# pilotage_moteur.net
KiCad netlist of a schematic drawn in Altium Designer
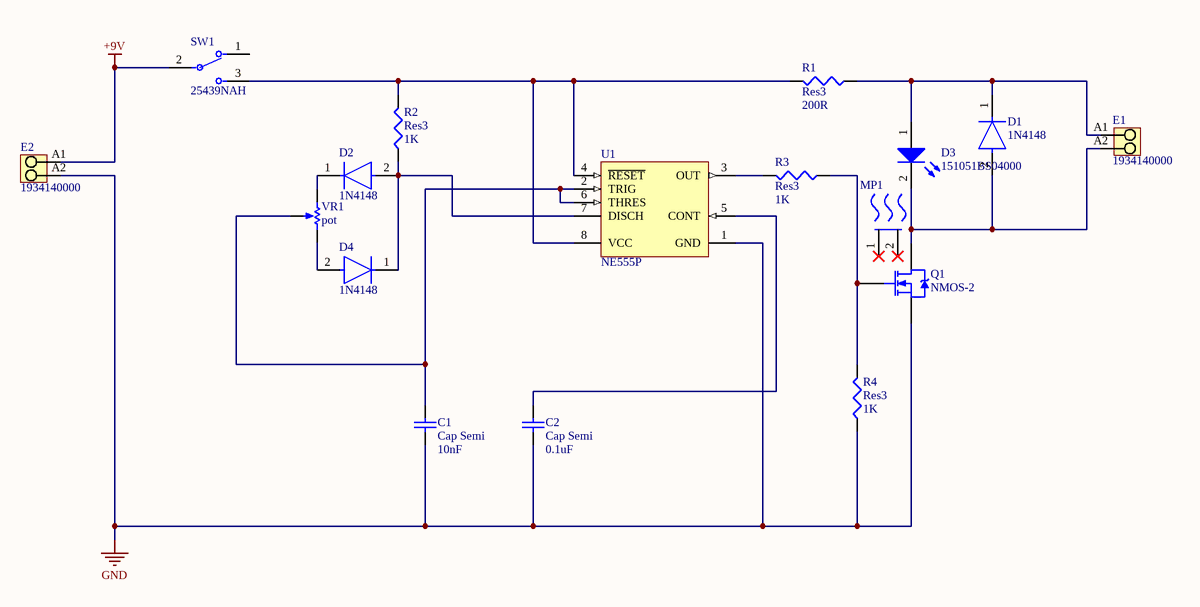
[diagram p0: pilotage moteur.SchDoc]

(export (version "E")
  (design (tool "Eeschema 10.0.6"))
  (components
    (comp (ref "C1")
      (value "Cap Semi")
      (footprint "C1206")
      (description "Capacitor (Semiconductor SIM Model)")
      (fields (field (name "ALTIUM_VALUE") "10nF") (field (name "PUBLISHER") "Altium Limited"))
      (libsource (lib "Miscellaneous Devices") (part "Cap Semi"))
    )
    (comp (ref "C2")
      (value "Cap Semi")
      (footprint "C1206")
      (description "Capacitor (Semiconductor SIM Model)")
      (fields (field (name "ALTIUM_VALUE") "0.1uF") (field (name "PUBLISHER") "Altium Limited"))
      (libsource (lib "Miscellaneous Devices") (part "Cap Semi"))
    )
    (comp (ref "D1")
      (value "1N4148")
      (footprint "FP-017AG-MFG")
      (description "DIODE GEN PURP 100V 200MA DO35")
      (fields (field (name "VOLTAGE") "100V"))
      (libsource (lib "Altium Content Vault") (part "d7152d700b627762746794eb795d46e"))
    )
    (comp (ref "D2")
      (value "1N4148")
      (footprint "FP-017AG-MFG")
      (description "DIODE GEN PURP 100V 200MA DO35")
      (fields (field (name "VOLTAGE") "100V"))
      (libsource (lib "Altium Content Vault") (part "d7152d700b627762746794eb795d46e"))
    )
    (comp (ref "D3")
      (value "151051BS04000")
      (footprint "WL-TMRC_D5.9H8.7")
      (libsource (lib "Altium Content Vault") (part "LED_Blue_1A-2K"))
    )
    (comp (ref "D4")
      (value "1N4148")
      (footprint "FP-017AG-MFG")
      (description "DIODE GEN PURP 100V 200MA DO35")
      (fields (field (name "VOLTAGE") "100V"))
      (libsource (lib "Altium Content Vault") (part "d7152d700b627762746794eb795d46e"))
    )
    (comp (ref "E1")
      (value "1934140000")
      (footprint "LU_10_16_90_02")
      (description "OMNIMATE Power - series LU")
      (fields (field (name "MANUFACTURER") "Weidmueller"))
      (libsource (lib "Altium Content Vault") (part "Terminal_02_1x02"))
    )
    (comp (ref "E2")
      (value "1934140000")
      (footprint "LU_10_16_90_02")
      (description "OMNIMATE Power - series LU")
      (fields (field (name "MANUFACTURER") "Weidmueller"))
      (libsource (lib "") (part "Terminal_02_1x02_1"))
    )
    (comp (ref "MP1")
      (value "E2A-T220-25E")
      (footprint "FP-E2A-T220-25E-MFG")
      (description "BLACK ANODIZED HEATSINK")
      (libsource (lib "Altium Content Vault") (part "3639d95c90db8693446ef71f1874dd6"))
    )
    (comp (ref "Q1")
      (value "NMOS-2")
      (footprint "TO-220AB")
      (description "N-Channel Power MOSFET")
      (fields (field (name "PUBLISHER") "Altium Limited"))
      (libsource (lib "Miscellaneous Devices") (part "NMOS-2"))
    )
    (comp (ref "R1")
      (value "Res3")
      (footprint "J1-0603")
      (description "Resistor")
      (fields (field (name "ALTIUM_VALUE") "200R") (field (name "PUBLISHER") "Altium Limited"))
      (libsource (lib "Miscellaneous Devices") (part "Res3"))
    )
    (comp (ref "R2")
      (value "Res3")
      (footprint "J1-0603")
      (description "Resistor")
      (fields (field (name "ALTIUM_VALUE") "1K") (field (name "PUBLISHER") "Altium Limited"))
      (libsource (lib "Miscellaneous Devices") (part "Res3"))
    )
    (comp (ref "R3")
      (value "Res3")
      (footprint "J1-0603")
      (description "Resistor")
      (fields (field (name "ALTIUM_VALUE") "1K") (field (name "PUBLISHER") "Altium Limited"))
      (libsource (lib "Miscellaneous Devices") (part "Res3"))
    )
    (comp (ref "R4")
      (value "Res3")
      (footprint "J1-0603")
      (description "Resistor")
      (fields (field (name "ALTIUM_VALUE") "1K") (field (name "PUBLISHER") "Altium Limited"))
      (libsource (lib "Miscellaneous Devices") (part "Res3"))
    )
    (comp (ref "SW1")
      (value "25439NAH")
      (footprint "FP-25439NAH-MFG")
      (description "SWITCH SLIDE SPDT 4A 125V")
      (libsource (lib "Altium Content Vault") (part "52c419afdc2a387c7d548259a9aeefb"))
    )
    (comp (ref "U1")
      (value "NE555P")
      (footprint "P0008A")
      (description "Precision Timer, 4.5 to 16 V, 0 to 70 degC, 8-Pin DIP, Pb-Free, Tube")
      (fields (field (name "MANUFACTURER") "TexasInstruments"))
      (libsource (lib "Altium Content Vault") (part "TI-NE555-P8"))
    )
    (comp (ref "VR1")
      (value "pot")
      (footprint "BOUR-3852A-282-103AL-3_V")
      (description "Diameter Panel Control, 10 KOhm, +/- 10%, 2 W, -1 to 125 degC, 3-Pin THD, RoHS, Bulk")
      (fields (field (name "TOLERANCE") "±10%") (field (name "MANUFACTURER") "Bourns"))
      (libsource (lib "Altium Content Vault") (part "RES-POT-3"))
    )
  )
  (nets
    (net (code "1") (name "+9V") (class "Default")
      (node (ref "E2") (pin "A1") (pinfunction "A1_A1") (pintype "passive"))
      (node (ref "SW1") (pin "2") (pinfunction "2_2") (pintype "passive"))
    )
    (net (code "2") (name "GND") (class "Default")
      (node (ref "C1") (pin "1") (pinfunction "1_1") (pintype "passive"))
      (node (ref "C2") (pin "1") (pinfunction "1_1") (pintype "passive"))
      (node (ref "E2") (pin "A2") (pinfunction "A2_A2") (pintype "passive"))
      (node (ref "Q1") (pin "3") (pinfunction "S_3") (pintype "passive"))
      (node (ref "R4") (pin "1") (pinfunction "1_1") (pintype "passive"))
      (node (ref "U1") (pin "1") (pinfunction "GND_1") (pintype "power_in"))
    )
    (net (code "3") (name "Net-(D1-A)") (class "Default")
      (node (ref "D1") (pin "2") (pinfunction "A_2") (pintype "passive"))
      (node (ref "D3") (pin "2") (pinfunction "K_2") (pintype "passive"))
      (node (ref "E1") (pin "A2") (pinfunction "A2_A2") (pintype "passive"))
      (node (ref "Q1") (pin "2") (pinfunction "D_2") (pintype "passive"))
    )
    (net (code "4") (name "Net-(D1-C)") (class "Default")
      (node (ref "D1") (pin "1") (pinfunction "C_1") (pintype "passive"))
      (node (ref "D3") (pin "1") (pinfunction "A_1") (pintype "passive"))
      (node (ref "E1") (pin "A1") (pinfunction "A1_A1") (pintype "passive"))
      (node (ref "R1") (pin "1") (pinfunction "1_1") (pintype "passive"))
    )
    (net (code "5") (name "Net-(D2-A)") (class "Default")
      (node (ref "D2") (pin "2") (pinfunction "A_2") (pintype "passive"))
      (node (ref "D4") (pin "1") (pinfunction "C_1") (pintype "passive"))
      (node (ref "R2") (pin "1") (pinfunction "1_1") (pintype "passive"))
      (node (ref "U1") (pin "7") (pinfunction "DISCH_7") (pintype "open_collector"))
    )
    (net (code "6") (name "Net-(D2-C)") (class "Default")
      (node (ref "D2") (pin "1") (pinfunction "C_1") (pintype "passive"))
      (node (ref "VR1") (pin "1") (pinfunction "CCW_1") (pintype "passive"))
    )
    (net (code "7") (name "Net-(D4-A)") (class "Default")
      (node (ref "D4") (pin "2") (pinfunction "A_2") (pintype "passive"))
      (node (ref "VR1") (pin "3") (pinfunction "CW_3") (pintype "passive"))
    )
    (net (code "8") (name "Net-(Q1-G)") (class "Default")
      (node (ref "Q1") (pin "1") (pinfunction "G_1") (pintype "passive"))
      (node (ref "R3") (pin "1") (pinfunction "1_1") (pintype "passive"))
      (node (ref "R4") (pin "2") (pinfunction "2_2") (pintype "passive"))
    )
    (net (code "9") (name "Net-(U1-CONT)") (class "Default")
      (node (ref "C2") (pin "2") (pinfunction "2_2") (pintype "passive"))
      (node (ref "U1") (pin "5") (pinfunction "CONT_5") (pintype "input"))
    )
    (net (code "10") (name "Net-(U1-OUT)") (class "Default")
      (node (ref "R3") (pin "2") (pinfunction "2_2") (pintype "passive"))
      (node (ref "U1") (pin "3") (pinfunction "OUT_3") (pintype "output"))
    )
    (net (code "11") (name "Net-(U1-THRES)") (class "Default")
      (node (ref "C1") (pin "2") (pinfunction "2_2") (pintype "passive"))
      (node (ref "U1") (pin "2") (pinfunction "TRIG_2") (pintype "input"))
      (node (ref "U1") (pin "6") (pinfunction "THRES_6") (pintype "input"))
      (node (ref "VR1") (pin "2") (pinfunction "S_2") (pintype "passive"))
    )
    (net (code "12") (name "Net-(U1-VCC)") (class "Default")
      (node (ref "R1") (pin "2") (pinfunction "2_2") (pintype "passive"))
      (node (ref "R2") (pin "2") (pinfunction "2_2") (pintype "passive"))
      (node (ref "SW1") (pin "3") (pinfunction "3_3") (pintype "passive"))
      (node (ref "U1") (pin "4") (pinfunction "~{RESET}_4") (pintype "input"))
      (node (ref "U1") (pin "8") (pinfunction "VCC_8") (pintype "power_in"))
    )
    (net (code "13") (name "unconnected-(MP1-MNT_1-Pad1)") (class "Default")
      (node (ref "MP1") (pin "1") (pinfunction "MNT_1_1") (pintype "passive+no_connect"))
    )
    (net (code "14") (name "unconnected-(MP1-MNT_2-Pad2)") (class "Default")
      (node (ref "MP1") (pin "2") (pinfunction "MNT_2_2") (pintype "passive+no_connect"))
    )
    (net (code "15") (name "unconnected-(SW1-Pad1)") (class "Default")
      (node (ref "SW1") (pin "1") (pinfunction "1_1") (pintype "passive"))
    )
  )
)
